# W-N-DM-V31_Display.net
KiCad netlist of a schematic drawn in Altium Designer
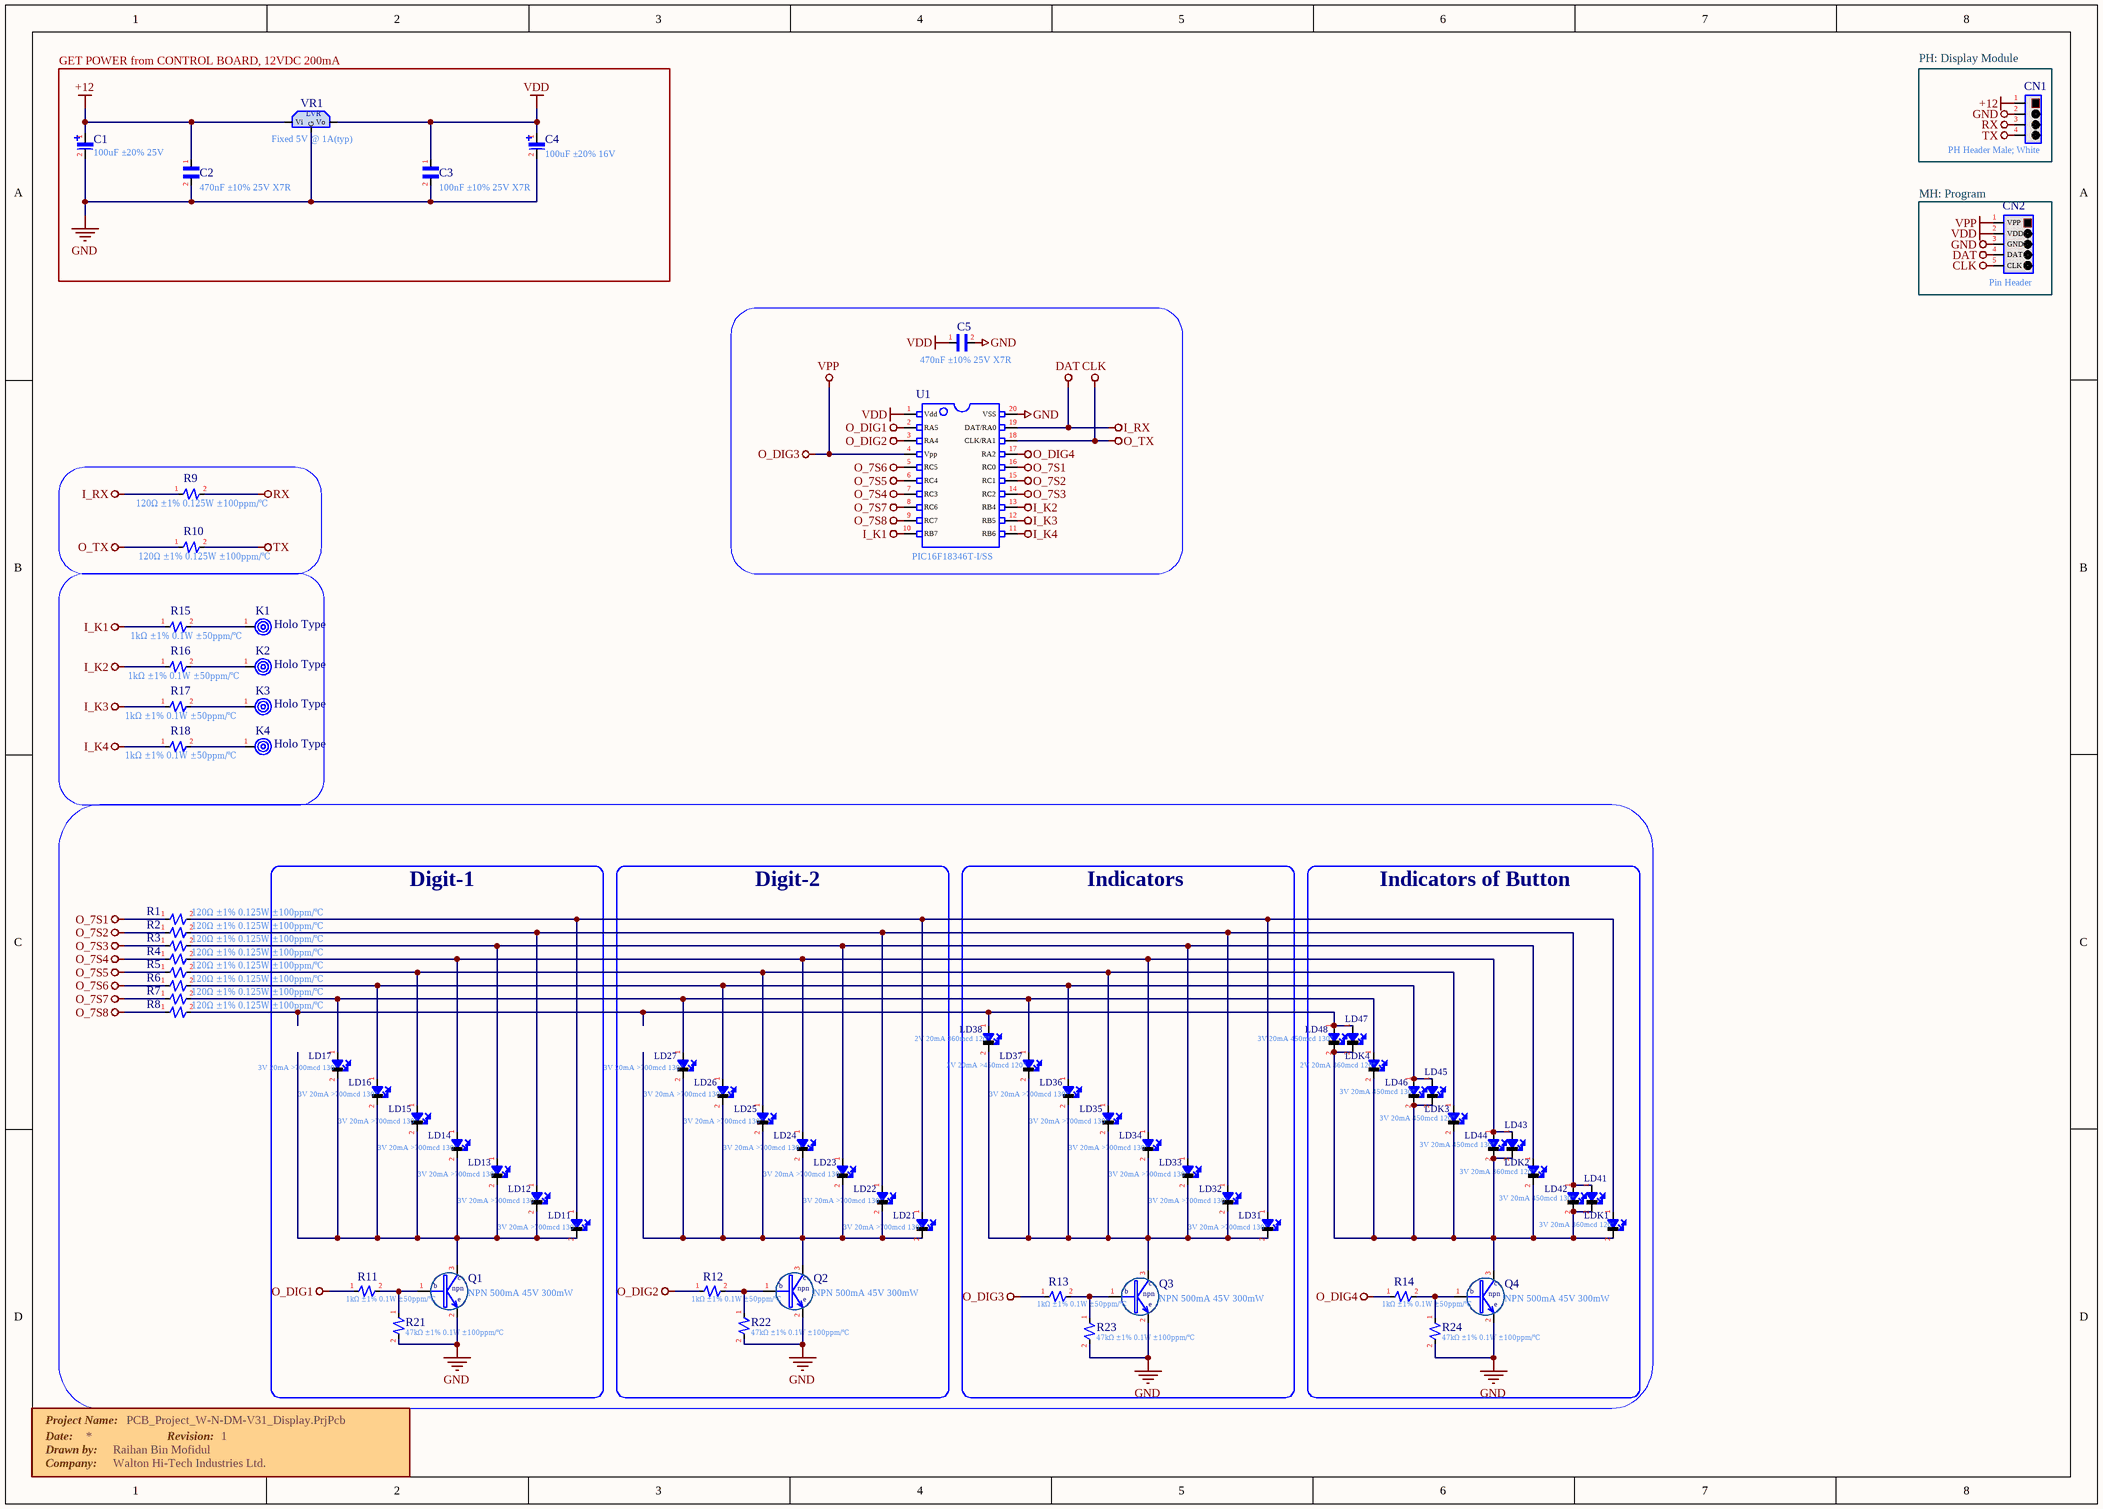
[diagram p0: W-N-DM-V31_Display.SchDoc]

(export (version "E")
  (design (tool "Eeschema 10.0.6"))
  (components
    (comp (ref "C1")
      (value "100uF ±20% 25V")
      (footprint "C_SMD_Ø6.3*5.4mm")
      (description "SMD,6.3x5.4mm Aluminum Electrolytic Capacitors - SMD RoHS")
      (libsource (lib "RBM_ALTIUM_SCH_LIBRARY") (part "Capacitor{gt}{gt} Polar"))
    )
    (comp (ref "C2")
      (value "470nF ±10% 25V X7R")
      (footprint "C_0603")
      (description "0603 Multilayer Ceramic Capacitors MLCC - SMD/SMT RoHS")
      (libsource (lib "RBM_ALTIUM_SCH_LIBRARY") (part "Capacitor{gt}{gt} Non-Polar"))
    )
    (comp (ref "C3")
      (value "100nF ±10% 25V X7R")
      (footprint "C_0603")
      (description "0603 Multilayer Ceramic Capacitors MLCC - SMD/SMT RoHS")
      (libsource (lib "RBM_ALTIUM_SCH_LIBRARY") (part "Capacitor{gt}{gt} Non-Polar"))
    )
    (comp (ref "C4")
      (value "100uF ±20% 16V")
      (footprint "C_SMD_Ø6.3*5.4mm")
      (description "SMD,6.3x5.4mm Aluminum Electrolytic Capacitors - SMD RoHS")
      (libsource (lib "RBM_ALTIUM_SCH_LIBRARY") (part "Capacitor{gt}{gt} Polar"))
    )
    (comp (ref "C5")
      (value "470nF ±10% 25V X7R")
      (footprint "C_0603")
      (description "0603 Multilayer Ceramic Capacitors MLCC - SMD/SMT RoHS")
      (libsource (lib "") (part "Capacitor{gt}{gt} Non-Polar_1"))
    )
    (comp (ref "CN1")
      (value "PH Header Male; White")
      (footprint "CN_4P_A2001WR-S-XP-LCP")
      (description "A2001WR-S-4P; Pin 0.079\"(2.00mm) 4 SMD,P=2mm Wire To Board / Wire To Wire Connector RoHS")
      (libsource (lib "RBM_ALTIUM_SCH_LIBRARY") (part "Connector{gt}{gt} 4Pins"))
    )
    (comp (ref "CN2")
      (value "Pin Header")
      (footprint "CN_PIC_MCU_Debugger_RightAngle")
      (libsource (lib "RBM_ALTIUM_SCH_LIBRARY") (part "Connector{gt}{gt} PIC Program"))
    )
    (comp (ref "K1")
      (value "Holo Type")
      (footprint "K_Cap-Touch_with_LED-Option")
      (libsource (lib "RBM_ALTIUM_SCH_LIBRARY") (part "Key{gt}{gt} Cap Touch"))
    )
    (comp (ref "K2")
      (value "Holo Type")
      (footprint "K_Cap-Touch_with_LED-Option")
      (libsource (lib "RBM_ALTIUM_SCH_LIBRARY") (part "Key{gt}{gt} Cap Touch"))
    )
    (comp (ref "K3")
      (value "Holo Type")
      (footprint "K_Cap-Touch_with_LED-Option")
      (libsource (lib "RBM_ALTIUM_SCH_LIBRARY") (part "Key{gt}{gt} Cap Touch"))
    )
    (comp (ref "K4")
      (value "Holo Type")
      (footprint "K_Cap-Touch_with_LED-Option")
      (libsource (lib "RBM_ALTIUM_SCH_LIBRARY") (part "Key{gt}{gt} Cap Touch"))
    )
    (comp (ref "LD11")
      (value "3V 20mA >700mcd 130°")
      (footprint "LED_SMD0603")
      (description "MHT192WDT-ICE; ICE-BLUE Color - 0603 Light Emitting Diodes (LED) RoHS")
      (libsource (lib "RBM_ALTIUM_SCH_LIBRARY") (part "LED{gt}{gt} General Purpose"))
    )
    (comp (ref "LD12")
      (value "3V 20mA >700mcd 130°")
      (footprint "LED_SMD0603")
      (description "MHT192WDT-ICE; ICE-BLUE Color - 0603 Light Emitting Diodes (LED) RoHS")
      (libsource (lib "RBM_ALTIUM_SCH_LIBRARY") (part "LED{gt}{gt} General Purpose"))
    )
    (comp (ref "LD13")
      (value "3V 20mA >700mcd 130°")
      (footprint "LED_SMD0603")
      (description "MHT192WDT-ICE; ICE-BLUE Color - 0603 Light Emitting Diodes (LED) RoHS")
      (libsource (lib "RBM_ALTIUM_SCH_LIBRARY") (part "LED{gt}{gt} General Purpose"))
    )
    (comp (ref "LD14")
      (value "3V 20mA >700mcd 130°")
      (footprint "LED_SMD0603")
      (description "MHT192WDT-ICE; ICE-BLUE Color - 0603 Light Emitting Diodes (LED) RoHS")
      (libsource (lib "RBM_ALTIUM_SCH_LIBRARY") (part "LED{gt}{gt} General Purpose"))
    )
    (comp (ref "LD15")
      (value "3V 20mA >700mcd 130°")
      (footprint "LED_SMD0603")
      (description "MHT192WDT-ICE; ICE-BLUE Color - 0603 Light Emitting Diodes (LED) RoHS")
      (libsource (lib "RBM_ALTIUM_SCH_LIBRARY") (part "LED{gt}{gt} General Purpose"))
    )
    (comp (ref "LD16")
      (value "3V 20mA >700mcd 130°")
      (footprint "LED_SMD0603")
      (description "MHT192WDT-ICE; ICE-BLUE Color - 0603 Light Emitting Diodes (LED) RoHS")
      (libsource (lib "RBM_ALTIUM_SCH_LIBRARY") (part "LED{gt}{gt} General Purpose"))
    )
    (comp (ref "LD17")
      (value "3V 20mA >700mcd 130°")
      (footprint "LED_SMD0603")
      (description "MHT192WDT-ICE; ICE-BLUE Color - 0603 Light Emitting Diodes (LED) RoHS")
      (libsource (lib "RBM_ALTIUM_SCH_LIBRARY") (part "LED{gt}{gt} General Purpose"))
    )
    (comp (ref "LD21")
      (value "3V 20mA >700mcd 130°")
      (footprint "LED_SMD0603")
      (description "MHT192WDT-ICE; ICE-BLUE Color - 0603 Light Emitting Diodes (LED) RoHS")
      (libsource (lib "RBM_ALTIUM_SCH_LIBRARY") (part "LED{gt}{gt} General Purpose"))
    )
    (comp (ref "LD22")
      (value "3V 20mA >700mcd 130°")
      (footprint "LED_SMD0603")
      (description "MHT192WDT-ICE; ICE-BLUE Color - 0603 Light Emitting Diodes (LED) RoHS")
      (libsource (lib "RBM_ALTIUM_SCH_LIBRARY") (part "LED{gt}{gt} General Purpose"))
    )
    (comp (ref "LD23")
      (value "3V 20mA >700mcd 130°")
      (footprint "LED_SMD0603")
      (description "MHT192WDT-ICE; ICE-BLUE Color - 0603 Light Emitting Diodes (LED) RoHS")
      (libsource (lib "RBM_ALTIUM_SCH_LIBRARY") (part "LED{gt}{gt} General Purpose"))
    )
    (comp (ref "LD24")
      (value "3V 20mA >700mcd 130°")
      (footprint "LED_SMD0603")
      (description "MHT192WDT-ICE; ICE-BLUE Color - 0603 Light Emitting Diodes (LED) RoHS")
      (libsource (lib "RBM_ALTIUM_SCH_LIBRARY") (part "LED{gt}{gt} General Purpose"))
    )
    (comp (ref "LD25")
      (value "3V 20mA >700mcd 130°")
      (footprint "LED_SMD0603")
      (description "MHT192WDT-ICE; ICE-BLUE Color - 0603 Light Emitting Diodes (LED) RoHS")
      (libsource (lib "RBM_ALTIUM_SCH_LIBRARY") (part "LED{gt}{gt} General Purpose"))
    )
    (comp (ref "LD26")
      (value "3V 20mA >700mcd 130°")
      (footprint "LED_SMD0603")
      (description "MHT192WDT-ICE; ICE-BLUE Color - 0603 Light Emitting Diodes (LED) RoHS")
      (libsource (lib "RBM_ALTIUM_SCH_LIBRARY") (part "LED{gt}{gt} General Purpose"))
    )
    (comp (ref "LD27")
      (value "3V 20mA >700mcd 130°")
      (footprint "LED_SMD0603")
      (description "MHT192WDT-ICE; ICE-BLUE Color - 0603 Light Emitting Diodes (LED) RoHS")
      (libsource (lib "RBM_ALTIUM_SCH_LIBRARY") (part "LED{gt}{gt} General Purpose"))
    )
    (comp (ref "LD31")
      (value "3V 20mA >700mcd 130°")
      (footprint "LED_SMD0603")
      (description "MHT192WDT-ICE; ICE-BLUE Color - 0603 Light Emitting Diodes (LED) RoHS")
      (libsource (lib "RBM_ALTIUM_SCH_LIBRARY") (part "LED{gt}{gt} General Purpose"))
    )
    (comp (ref "LD32")
      (value "3V 20mA >700mcd 130°")
      (footprint "LED_SMD0603")
      (description "MHT192WDT-ICE; ICE-BLUE Color - 0603 Light Emitting Diodes (LED) RoHS")
      (libsource (lib "RBM_ALTIUM_SCH_LIBRARY") (part "LED{gt}{gt} General Purpose"))
    )
    (comp (ref "LD33")
      (value "3V 20mA >700mcd 130°")
      (footprint "LED_SMD0603")
      (description "MHT192WDT-ICE; ICE-BLUE Color - 0603 Light Emitting Diodes (LED) RoHS")
      (libsource (lib "RBM_ALTIUM_SCH_LIBRARY") (part "LED{gt}{gt} General Purpose"))
    )
    (comp (ref "LD34")
      (value "3V 20mA >700mcd 130°")
      (footprint "LED_SMD0603")
      (description "MHT192WDT-ICE; ICE-BLUE Color - 0603 Light Emitting Diodes (LED) RoHS")
      (libsource (lib "RBM_ALTIUM_SCH_LIBRARY") (part "LED{gt}{gt} General Purpose"))
    )
    (comp (ref "LD35")
      (value "3V 20mA >700mcd 130°")
      (footprint "LED_SMD0603")
      (description "MHT192WDT-ICE; ICE-BLUE Color - 0603 Light Emitting Diodes (LED) RoHS")
      (libsource (lib "RBM_ALTIUM_SCH_LIBRARY") (part "LED{gt}{gt} General Purpose"))
    )
    (comp (ref "LD36")
      (value "3V 20mA >700mcd 130°")
      (footprint "LED_SMD0603")
      (description "MHT192WDT-ICE; ICE-BLUE Color - 0603 Light Emitting Diodes (LED) RoHS")
      (libsource (lib "RBM_ALTIUM_SCH_LIBRARY") (part "LED{gt}{gt} General Purpose"))
    )
    (comp (ref "LD37")
      (value "2V 20mA >450mcd 120°")
      (footprint "LED_SMD0603")
      (description "MHT192URCT; Brilliant Red Color - 0603 Light Emitting Diodes (LED) RoHS")
      (libsource (lib "RBM_ALTIUM_SCH_LIBRARY") (part "LED{gt}{gt} General Purpose"))
    )
    (comp (ref "LD38")
      (value "2V 20mA 360mcd 120°")
      (footprint "LED_SMD0603")
      (description "MHT192USCT; Brilliant Orange Color - 0603 Light Emitting Diodes (LED) RoHS")
      (libsource (lib "RBM_ALTIUM_SCH_LIBRARY") (part "LED{gt}{gt} General Purpose"))
    )
    (comp (ref "LD41")
      (value "3V 20mA 450mcd 130°")
      (footprint "LED_SMD0603")
      (description "MHT192WDT-C2; WHITE Color - 0603 Light Emitting Diodes (LED) RoHS")
      (libsource (lib "RBM_ALTIUM_SCH_LIBRARY") (part "LED{gt}{gt} General Purpose"))
    )
    (comp (ref "LD42")
      (value "3V 20mA 450mcd 130°")
      (footprint "LED_SMD0603")
      (description "MHT192WDT-C2; WHITE Color - 0603 Light Emitting Diodes (LED) RoHS")
      (libsource (lib "RBM_ALTIUM_SCH_LIBRARY") (part "LED{gt}{gt} General Purpose"))
    )
    (comp (ref "LD43")
      (value "3V 20mA 450mcd 130°")
      (footprint "LED_SMD0603")
      (description "MHT192WDT-C2; WHITE Color - 0603 Light Emitting Diodes (LED) RoHS")
      (libsource (lib "RBM_ALTIUM_SCH_LIBRARY") (part "LED{gt}{gt} General Purpose"))
    )
    (comp (ref "LD44")
      (value "3V 20mA 450mcd 130°")
      (footprint "LED_SMD0603")
      (description "MHT192WDT-C2; WHITE Color - 0603 Light Emitting Diodes (LED) RoHS")
      (libsource (lib "RBM_ALTIUM_SCH_LIBRARY") (part "LED{gt}{gt} General Purpose"))
    )
    (comp (ref "LD45")
      (value "3V 20mA 450mcd 130°")
      (footprint "LED_SMD0603")
      (description "MHT192WDT-C2; WHITE Color - 0603 Light Emitting Diodes (LED) RoHS")
      (libsource (lib "RBM_ALTIUM_SCH_LIBRARY") (part "LED{gt}{gt} General Purpose"))
    )
    (comp (ref "LD46")
      (value "3V 20mA 450mcd 130°")
      (footprint "LED_SMD0603")
      (description "MHT192WDT-C2; WHITE Color - 0603 Light Emitting Diodes (LED) RoHS")
      (libsource (lib "RBM_ALTIUM_SCH_LIBRARY") (part "LED{gt}{gt} General Purpose"))
    )
    (comp (ref "LD47")
      (value "3V 20mA 450mcd 130°")
      (footprint "LED_SMD0603")
      (description "MHT192WDT-C2; WHITE Color - 0603 Light Emitting Diodes (LED) RoHS")
      (libsource (lib "RBM_ALTIUM_SCH_LIBRARY") (part "LED{gt}{gt} General Purpose"))
    )
    (comp (ref "LD48")
      (value "3V 20mA 450mcd 130°")
      (footprint "LED_SMD0603")
      (description "MHT192WDT-C2; WHITE Color - 0603 Light Emitting Diodes (LED) RoHS")
      (libsource (lib "") (part "LED{gt}{gt} General Purpose_1"))
    )
    (comp (ref "LDK1")
      (value "3V 20mA 360mcd 120°")
      (footprint "LED_SMD0603")
      (description "MHT192UBCT; Brilliant Blue Color - 0603 Light Emitting Diodes (LED) RoHS")
      (libsource (lib "RBM_ALTIUM_SCH_LIBRARY") (part "LED{gt}{gt} General Purpose"))
    )
    (comp (ref "LDK2")
      (value "3V 20mA 360mcd 120°")
      (footprint "LED_SMD0603")
      (description "MHT192UBCT; Brilliant Blue Color - 0603 Light Emitting Diodes (LED) RoHS")
      (libsource (lib "RBM_ALTIUM_SCH_LIBRARY") (part "LED{gt}{gt} General Purpose"))
    )
    (comp (ref "LDK3")
      (value "3V 20mA 450mcd 120°")
      (footprint "LED_SMD0603")
      (description "MHT192UGCT; Brilliant Green Color - 0603 Light Emitting Diodes (LED) RoHS")
      (libsource (lib "RBM_ALTIUM_SCH_LIBRARY") (part "LED{gt}{gt} General Purpose"))
    )
    (comp (ref "LDK4")
      (value "2V 20mA 360mcd 120°")
      (footprint "LED_SMD0603")
      (description "MHT192USCT; Brilliant Orange Color - 0603 Light Emitting Diodes (LED) RoHS")
      (libsource (lib "RBM_ALTIUM_SCH_LIBRARY") (part "LED{gt}{gt} General Purpose"))
    )
    (comp (ref "Q1")
      (value "NPN 500mA 45V 300mW")
      (footprint "Q_SOT-23_NPN")
      (description "BC817-40; SOT-23(SOT-23-3) Transistors (NPN/PNP) RoHS")
      (libsource (lib "RBM_ALTIUM_SCH_LIBRARY") (part "Transistor{gt}{gt} BJT npn"))
    )
    (comp (ref "Q2")
      (value "NPN 500mA 45V 300mW")
      (footprint "Q_SOT-23_NPN")
      (description "BC817-40; SOT-23(SOT-23-3) Transistors (NPN/PNP) RoHS")
      (libsource (lib "RBM_ALTIUM_SCH_LIBRARY") (part "Transistor{gt}{gt} BJT npn"))
    )
    (comp (ref "Q3")
      (value "NPN 500mA 45V 300mW")
      (footprint "Q_SOT-23_NPN")
      (description "BC817-40; SOT-23(SOT-23-3) Transistors (NPN/PNP) RoHS")
      (libsource (lib "RBM_ALTIUM_SCH_LIBRARY") (part "Transistor{gt}{gt} BJT npn"))
    )
    (comp (ref "Q4")
      (value "NPN 500mA 45V 300mW")
      (footprint "Q_SOT-23_NPN")
      (description "BC817-40; SOT-23(SOT-23-3) Transistors (NPN/PNP) RoHS")
      (libsource (lib "RBM_ALTIUM_SCH_LIBRARY") (part "Transistor{gt}{gt} BJT npn"))
    )
    (comp (ref "R1")
      (value "120Ω ±1% 0.125W ±100ppm/℃")
      (footprint "R_0603")
      (description "RK73H1JTTD1200F; 0603 Chip Resistor - Surface Mount RoHS")
      (libsource (lib "RBM_ALTIUM_SCH_LIBRARY") (part "Resistor{gt}{gt} General Purpose"))
    )
    (comp (ref "R2")
      (value "120Ω ±1% 0.125W ±100ppm/℃")
      (footprint "R_0603")
      (description "RK73H1JTTD1200F; 0603 Chip Resistor - Surface Mount RoHS")
      (libsource (lib "RBM_ALTIUM_SCH_LIBRARY") (part "Resistor{gt}{gt} General Purpose"))
    )
    (comp (ref "R3")
      (value "120Ω ±1% 0.125W ±100ppm/℃")
      (footprint "R_0603")
      (description "RK73H1JTTD1200F; 0603 Chip Resistor - Surface Mount RoHS")
      (libsource (lib "RBM_ALTIUM_SCH_LIBRARY") (part "Resistor{gt}{gt} General Purpose"))
    )
    (comp (ref "R4")
      (value "120Ω ±1% 0.125W ±100ppm/℃")
      (footprint "R_0603")
      (description "RK73H1JTTD1200F; 0603 Chip Resistor - Surface Mount RoHS")
      (libsource (lib "RBM_ALTIUM_SCH_LIBRARY") (part "Resistor{gt}{gt} General Purpose"))
    )
    (comp (ref "R5")
      (value "120Ω ±1% 0.125W ±100ppm/℃")
      (footprint "R_0603")
      (description "RK73H1JTTD1200F; 0603 Chip Resistor - Surface Mount RoHS")
      (libsource (lib "RBM_ALTIUM_SCH_LIBRARY") (part "Resistor{gt}{gt} General Purpose"))
    )
    (comp (ref "R6")
      (value "120Ω ±1% 0.125W ±100ppm/℃")
      (footprint "R_0603")
      (description "RK73H1JTTD1200F; 0603 Chip Resistor - Surface Mount RoHS")
      (libsource (lib "RBM_ALTIUM_SCH_LIBRARY") (part "Resistor{gt}{gt} General Purpose"))
    )
    (comp (ref "R7")
      (value "120Ω ±1% 0.125W ±100ppm/℃")
      (footprint "R_0603")
      (description "RK73H1JTTD1200F; 0603 Chip Resistor - Surface Mount RoHS")
      (libsource (lib "RBM_ALTIUM_SCH_LIBRARY") (part "Resistor{gt}{gt} General Purpose"))
    )
    (comp (ref "R8")
      (value "120Ω ±1% 0.125W ±100ppm/℃")
      (footprint "R_0603")
      (description "RK73H1JTTD1200F; 0603 Chip Resistor - Surface Mount RoHS")
      (libsource (lib "RBM_ALTIUM_SCH_LIBRARY") (part "Resistor{gt}{gt} General Purpose"))
    )
    (comp (ref "R9")
      (value "120Ω ±1% 0.125W ±100ppm/℃")
      (footprint "R_0603")
      (description "RK73H1JTTD1200F; 0603 Chip Resistor - Surface Mount RoHS")
      (libsource (lib "RBM_ALTIUM_SCH_LIBRARY") (part "Resistor{gt}{gt} General Purpose"))
    )
    (comp (ref "R10")
      (value "120Ω ±1% 0.125W ±100ppm/℃")
      (footprint "R_0603")
      (description "RK73H1JTTD1200F; 0603 Chip Resistor - Surface Mount RoHS")
      (libsource (lib "RBM_ALTIUM_SCH_LIBRARY") (part "Resistor{gt}{gt} General Purpose"))
    )
    (comp (ref "R11")
      (value "1kΩ ±1% 0.1W ±50ppm/℃")
      (footprint "R_0603")
      (description "RK73G1JTTD1001F; 0603 Chip Resistor - Surface Mount RoHS")
      (libsource (lib "RBM_ALTIUM_SCH_LIBRARY") (part "Resistor{gt}{gt} General Purpose"))
    )
    (comp (ref "R12")
      (value "1kΩ ±1% 0.1W ±50ppm/℃")
      (footprint "R_0603")
      (description "RK73G1JTTD1001F; 0603 Chip Resistor - Surface Mount RoHS")
      (libsource (lib "RBM_ALTIUM_SCH_LIBRARY") (part "Resistor{gt}{gt} General Purpose"))
    )
    (comp (ref "R13")
      (value "1kΩ ±1% 0.1W ±50ppm/℃")
      (footprint "R_0603")
      (description "RK73G1JTTD1001F; 0603 Chip Resistor - Surface Mount RoHS")
      (libsource (lib "RBM_ALTIUM_SCH_LIBRARY") (part "Resistor{gt}{gt} General Purpose"))
    )
    (comp (ref "R14")
      (value "1kΩ ±1% 0.1W ±50ppm/℃")
      (footprint "R_0603")
      (description "RK73G1JTTD1001F; 0603 Chip Resistor - Surface Mount RoHS")
      (libsource (lib "RBM_ALTIUM_SCH_LIBRARY") (part "Resistor{gt}{gt} General Purpose"))
    )
    (comp (ref "R15")
      (value "1kΩ ±1% 0.1W ±50ppm/℃")
      (footprint "R_0603")
      (description "RK73G1JTTD1001F; 0603 Chip Resistor - Surface Mount RoHS")
      (libsource (lib "RBM_ALTIUM_SCH_LIBRARY") (part "Resistor{gt}{gt} General Purpose"))
    )
    (comp (ref "R16")
      (value "1kΩ ±1% 0.1W ±50ppm/℃")
      (footprint "R_0603")
      (description "RK73G1JTTD1001F; 0603 Chip Resistor - Surface Mount RoHS")
      (libsource (lib "RBM_ALTIUM_SCH_LIBRARY") (part "Resistor{gt}{gt} General Purpose"))
    )
    (comp (ref "R17")
      (value "1kΩ ±1% 0.1W ±50ppm/℃")
      (footprint "R_0603")
      (description "RK73G1JTTD1001F; 0603 Chip Resistor - Surface Mount RoHS")
      (libsource (lib "RBM_ALTIUM_SCH_LIBRARY") (part "Resistor{gt}{gt} General Purpose"))
    )
    (comp (ref "R18")
      (value "1kΩ ±1% 0.1W ±50ppm/℃")
      (footprint "R_0603")
      (description "RK73G1JTTD1001F; 0603 Chip Resistor - Surface Mount RoHS")
      (libsource (lib "RBM_ALTIUM_SCH_LIBRARY") (part "Resistor{gt}{gt} General Purpose"))
    )
    (comp (ref "R21")
      (value "47kΩ ±1% 0.1W ±100ppm/℃")
      (footprint "R_0603")
      (description "RK73H1JTTD4702F; 0603 Chip Resistor - Surface Mount RoHS")
      (libsource (lib "RBM_ALTIUM_SCH_LIBRARY") (part "Resistor{gt}{gt} General Purpose"))
    )
    (comp (ref "R22")
      (value "47kΩ ±1% 0.1W ±100ppm/℃")
      (footprint "R_0603")
      (description "RK73H1JTTD4702F; 0603 Chip Resistor - Surface Mount RoHS")
      (libsource (lib "RBM_ALTIUM_SCH_LIBRARY") (part "Resistor{gt}{gt} General Purpose"))
    )
    (comp (ref "R23")
      (value "47kΩ ±1% 0.1W ±100ppm/℃")
      (footprint "R_0603")
      (description "RK73H1JTTD4702F; 0603 Chip Resistor - Surface Mount RoHS")
      (libsource (lib "RBM_ALTIUM_SCH_LIBRARY") (part "Resistor{gt}{gt} General Purpose"))
    )
    (comp (ref "R24")
      (value "47kΩ ±1% 0.1W ±100ppm/℃")
      (footprint "R_0603")
      (description "RK73H1JTTD4702F; 0603 Chip Resistor - Surface Mount RoHS")
      (libsource (lib "RBM_ALTIUM_SCH_LIBRARY") (part "Resistor{gt}{gt} General Purpose"))
    )
    (comp (ref "U1")
      (value "PIC16F18346T-I/SS")
      (footprint "U_PIC_20pin_SSOP")
      (libsource (lib "RBM_ALTIUM_SCH_LIBRARY") (part "IC{gt}{gt} PIC 20Pins"))
    )
    (comp (ref "VR1")
      (value "Fixed 5V @ 1A(typ)")
      (footprint "VR_TO-252-2(DPAK)")
      (description "CJ78D05/MC7805BDTRKG; TO-252-2(DPAK) Dropout Regulators(LDO) RoHS")
      (libsource (lib "RBM_ALTIUM_SCH_LIBRARY") (part "Voltage Regulator"))
    )
  )
  (nets
    (net (code "1") (name "+12") (class "Default")
      (node (ref "C1") (pin "1") (pinfunction "1_1") (pintype "passive"))
      (node (ref "C2") (pin "1") (pinfunction "1_1") (pintype "passive"))
      (node (ref "CN1") (pin "1") (pinfunction "1_1") (pintype "passive"))
      (node (ref "VR1") (pin "V-IN") (pinfunction "Vi_V-IN") (pintype "passive"))
    )
    (net (code "2") (name "CLK") (class "Default")
      (node (ref "CN2") (pin "5") (pinfunction "CLK_5") (pintype "passive"))
      (node (ref "R10") (pin "1") (pinfunction "1_1") (pintype "passive"))
      (node (ref "U1") (pin "18") (pinfunction "CLK/RA1_18") (pintype "passive"))
    )
    (net (code "3") (name "DAT") (class "Default")
      (node (ref "CN2") (pin "4") (pinfunction "DAT_4") (pintype "passive"))
      (node (ref "R9") (pin "1") (pinfunction "1_1") (pintype "passive"))
      (node (ref "U1") (pin "19") (pinfunction "DAT/RA0_19") (pintype "passive"))
    )
    (net (code "4") (name "GND") (class "Default")
      (node (ref "C1") (pin "2") (pinfunction "2_2") (pintype "passive"))
      (node (ref "C2") (pin "2") (pinfunction "2_2") (pintype "passive"))
      (node (ref "C3") (pin "2") (pinfunction "2_2") (pintype "passive"))
      (node (ref "C4") (pin "2") (pinfunction "2_2") (pintype "passive"))
      (node (ref "C5") (pin "2") (pinfunction "2_2") (pintype "passive"))
      (node (ref "CN1") (pin "2") (pinfunction "2_2") (pintype "passive"))
      (node (ref "CN2") (pin "3") (pinfunction "GND_3") (pintype "passive"))
      (node (ref "Q1") (pin "2") (pinfunction "Emitter_2") (pintype "passive"))
      (node (ref "Q2") (pin "2") (pinfunction "Emitter_2") (pintype "passive"))
      (node (ref "Q3") (pin "2") (pinfunction "Emitter_2") (pintype "passive"))
      (node (ref "Q4") (pin "2") (pinfunction "Emitter_2") (pintype "passive"))
      (node (ref "R21") (pin "2") (pinfunction "2_2") (pintype "passive"))
      (node (ref "R22") (pin "2") (pinfunction "2_2") (pintype "passive"))
      (node (ref "R23") (pin "2") (pinfunction "2_2") (pintype "passive"))
      (node (ref "R24") (pin "2") (pinfunction "2_2") (pintype "passive"))
      (node (ref "U1") (pin "20") (pinfunction "VSS_20") (pintype "passive"))
      (node (ref "VR1") (pin "GND") (pinfunction "G_GND") (pintype "passive"))
    )
    (net (code "5") (name "I_K1") (class "Default")
      (node (ref "R15") (pin "1") (pinfunction "1_1") (pintype "passive"))
      (node (ref "U1") (pin "10") (pinfunction "RB7_10") (pintype "passive"))
    )
    (net (code "6") (name "I_K2") (class "Default")
      (node (ref "R16") (pin "1") (pinfunction "1_1") (pintype "passive"))
      (node (ref "U1") (pin "13") (pinfunction "RB4_13") (pintype "passive"))
    )
    (net (code "7") (name "I_K3") (class "Default")
      (node (ref "R17") (pin "1") (pinfunction "1_1") (pintype "passive"))
      (node (ref "U1") (pin "12") (pinfunction "RB5_12") (pintype "passive"))
    )
    (net (code "8") (name "I_K4") (class "Default")
      (node (ref "R18") (pin "1") (pinfunction "1_1") (pintype "passive"))
      (node (ref "U1") (pin "11") (pinfunction "RB6_11") (pintype "passive"))
    )
    (net (code "9") (name "Net-(K1-Pad1)") (class "Default")
      (node (ref "K1") (pin "1") (pinfunction "1_1") (pintype "passive"))
      (node (ref "R15") (pin "2") (pinfunction "2_2") (pintype "passive"))
    )
    (net (code "10") (name "Net-(K2-Pad1)") (class "Default")
      (node (ref "K2") (pin "1") (pinfunction "1_1") (pintype "passive"))
      (node (ref "R16") (pin "2") (pinfunction "2_2") (pintype "passive"))
    )
    (net (code "11") (name "Net-(K3-Pad1)") (class "Default")
      (node (ref "K3") (pin "1") (pinfunction "1_1") (pintype "passive"))
      (node (ref "R17") (pin "2") (pinfunction "2_2") (pintype "passive"))
    )
    (net (code "12") (name "Net-(K4-Pad1)") (class "Default")
      (node (ref "K4") (pin "1") (pinfunction "1_1") (pintype "passive"))
      (node (ref "R18") (pin "2") (pinfunction "2_2") (pintype "passive"))
    )
    (net (code "13") (name "Net-(LD11-vdd)") (class "Default")
      (node (ref "LD11") (pin "1") (pinfunction "vdd_1") (pintype "passive"))
      (node (ref "LD21") (pin "1") (pinfunction "vdd_1") (pintype "passive"))
      (node (ref "LD31") (pin "1") (pinfunction "vdd_1") (pintype "passive"))
      (node (ref "LDK1") (pin "1") (pinfunction "vdd_1") (pintype "passive"))
      (node (ref "R1") (pin "2") (pinfunction "2_2") (pintype "passive"))
    )
    (net (code "14") (name "Net-(LD11-vss)") (class "Default")
      (node (ref "LD11") (pin "2") (pinfunction "vss_2") (pintype "passive"))
      (node (ref "LD12") (pin "2") (pinfunction "vss_2") (pintype "passive"))
      (node (ref "LD13") (pin "2") (pinfunction "vss_2") (pintype "passive"))
      (node (ref "LD14") (pin "2") (pinfunction "vss_2") (pintype "passive"))
      (node (ref "LD15") (pin "2") (pinfunction "vss_2") (pintype "passive"))
      (node (ref "LD16") (pin "2") (pinfunction "vss_2") (pintype "passive"))
      (node (ref "LD17") (pin "2") (pinfunction "vss_2") (pintype "passive"))
      (node (ref "Q1") (pin "3") (pinfunction "Collector_3") (pintype "passive"))
    )
    (net (code "15") (name "Net-(LD12-vdd)") (class "Default")
      (node (ref "LD12") (pin "1") (pinfunction "vdd_1") (pintype "passive"))
      (node (ref "LD22") (pin "1") (pinfunction "vdd_1") (pintype "passive"))
      (node (ref "LD32") (pin "1") (pinfunction "vdd_1") (pintype "passive"))
      (node (ref "LD41") (pin "1") (pinfunction "vdd_1") (pintype "passive"))
      (node (ref "LD42") (pin "1") (pinfunction "vdd_1") (pintype "passive"))
      (node (ref "R2") (pin "2") (pinfunction "2_2") (pintype "passive"))
    )
    (net (code "16") (name "Net-(LD13-vdd)") (class "Default")
      (node (ref "LD13") (pin "1") (pinfunction "vdd_1") (pintype "passive"))
      (node (ref "LD23") (pin "1") (pinfunction "vdd_1") (pintype "passive"))
      (node (ref "LD33") (pin "1") (pinfunction "vdd_1") (pintype "passive"))
      (node (ref "LDK2") (pin "1") (pinfunction "vdd_1") (pintype "passive"))
      (node (ref "R3") (pin "2") (pinfunction "2_2") (pintype "passive"))
    )
    (net (code "17") (name "Net-(LD14-vdd)") (class "Default")
      (node (ref "LD14") (pin "1") (pinfunction "vdd_1") (pintype "passive"))
      (node (ref "LD24") (pin "1") (pinfunction "vdd_1") (pintype "passive"))
      (node (ref "LD34") (pin "1") (pinfunction "vdd_1") (pintype "passive"))
      (node (ref "LD43") (pin "1") (pinfunction "vdd_1") (pintype "passive"))
      (node (ref "LD44") (pin "1") (pinfunction "vdd_1") (pintype "passive"))
      (node (ref "R4") (pin "2") (pinfunction "2_2") (pintype "passive"))
    )
    (net (code "18") (name "Net-(LD15-vdd)") (class "Default")
      (node (ref "LD15") (pin "1") (pinfunction "vdd_1") (pintype "passive"))
      (node (ref "LD25") (pin "1") (pinfunction "vdd_1") (pintype "passive"))
      (node (ref "LD35") (pin "1") (pinfunction "vdd_1") (pintype "passive"))
      (node (ref "LDK3") (pin "1") (pinfunction "vdd_1") (pintype "passive"))
      (node (ref "R5") (pin "2") (pinfunction "2_2") (pintype "passive"))
    )
    (net (code "19") (name "Net-(LD16-vdd)") (class "Default")
      (node (ref "LD16") (pin "1") (pinfunction "vdd_1") (pintype "passive"))
      (node (ref "LD26") (pin "1") (pinfunction "vdd_1") (pintype "passive"))
      (node (ref "LD36") (pin "1") (pinfunction "vdd_1") (pintype "passive"))
      (node (ref "LD45") (pin "1") (pinfunction "vdd_1") (pintype "passive"))
      (node (ref "LD46") (pin "1") (pinfunction "vdd_1") (pintype "passive"))
      (node (ref "R6") (pin "2") (pinfunction "2_2") (pintype "passive"))
    )
    (net (code "20") (name "Net-(LD17-vdd)") (class "Default")
      (node (ref "LD17") (pin "1") (pinfunction "vdd_1") (pintype "passive"))
      (node (ref "LD27") (pin "1") (pinfunction "vdd_1") (pintype "passive"))
      (node (ref "LD37") (pin "1") (pinfunction "vdd_1") (pintype "passive"))
      (node (ref "LDK4") (pin "1") (pinfunction "vdd_1") (pintype "passive"))
      (node (ref "R7") (pin "2") (pinfunction "2_2") (pintype "passive"))
    )
    (net (code "21") (name "Net-(LD21-vss)") (class "Default")
      (node (ref "LD21") (pin "2") (pinfunction "vss_2") (pintype "passive"))
      (node (ref "LD22") (pin "2") (pinfunction "vss_2") (pintype "passive"))
      (node (ref "LD23") (pin "2") (pinfunction "vss_2") (pintype "passive"))
      (node (ref "LD24") (pin "2") (pinfunction "vss_2") (pintype "passive"))
      (node (ref "LD25") (pin "2") (pinfunction "vss_2") (pintype "passive"))
      (node (ref "LD26") (pin "2") (pinfunction "vss_2") (pintype "passive"))
      (node (ref "LD27") (pin "2") (pinfunction "vss_2") (pintype "passive"))
      (node (ref "Q2") (pin "3") (pinfunction "Collector_3") (pintype "passive"))
    )
    (net (code "22") (name "Net-(LD31-vss)") (class "Default")
      (node (ref "LD31") (pin "2") (pinfunction "vss_2") (pintype "passive"))
      (node (ref "LD32") (pin "2") (pinfunction "vss_2") (pintype "passive"))
      (node (ref "LD33") (pin "2") (pinfunction "vss_2") (pintype "passive"))
      (node (ref "LD34") (pin "2") (pinfunction "vss_2") (pintype "passive"))
      (node (ref "LD35") (pin "2") (pinfunction "vss_2") (pintype "passive"))
      (node (ref "LD36") (pin "2") (pinfunction "vss_2") (pintype "passive"))
      (node (ref "LD37") (pin "2") (pinfunction "vss_2") (pintype "passive"))
      (node (ref "LD38") (pin "2") (pinfunction "vss_2") (pintype "passive"))
      (node (ref "Q3") (pin "3") (pinfunction "Collector_3") (pintype "passive"))
    )
    (net (code "23") (name "Net-(LD38-vdd)") (class "Default")
      (node (ref "LD38") (pin "1") (pinfunction "vdd_1") (pintype "passive"))
      (node (ref "LD47") (pin "1") (pinfunction "vdd_1") (pintype "passive"))
      (node (ref "LD48") (pin "1") (pinfunction "vdd_1") (pintype "passive"))
      (node (ref "R8") (pin "2") (pinfunction "2_2") (pintype "passive"))
    )
    (net (code "24") (name "Net-(LD41-vss)") (class "Default")
      (node (ref "LD41") (pin "2") (pinfunction "vss_2") (pintype "passive"))
      (node (ref "LD42") (pin "2") (pinfunction "vss_2") (pintype "passive"))
      (node (ref "LD43") (pin "2") (pinfunction "vss_2") (pintype "passive"))
      (node (ref "LD44") (pin "2") (pinfunction "vss_2") (pintype "passive"))
      (node (ref "LD45") (pin "2") (pinfunction "vss_2") (pintype "passive"))
      (node (ref "LD46") (pin "2") (pinfunction "vss_2") (pintype "passive"))
      (node (ref "LD47") (pin "2") (pinfunction "vss_2") (pintype "passive"))
      (node (ref "LD48") (pin "2") (pinfunction "vss_2") (pintype "passive"))
      (node (ref "LDK1") (pin "2") (pinfunction "vss_2") (pintype "passive"))
      (node (ref "LDK2") (pin "2") (pinfunction "vss_2") (pintype "passive"))
      (node (ref "LDK3") (pin "2") (pinfunction "vss_2") (pintype "passive"))
      (node (ref "LDK4") (pin "2") (pinfunction "vss_2") (pintype "passive"))
      (node (ref "Q4") (pin "3") (pinfunction "Collector_3") (pintype "passive"))
    )
    (net (code "25") (name "Net-(Q1-Base)") (class "Default")
      (node (ref "Q1") (pin "1") (pinfunction "Base_1") (pintype "passive"))
      (node (ref "R11") (pin "2") (pinfunction "2_2") (pintype "passive"))
      (node (ref "R21") (pin "1") (pinfunction "1_1") (pintype "passive"))
    )
    (net (code "26") (name "Net-(Q2-Base)") (class "Default")
      (node (ref "Q2") (pin "1") (pinfunction "Base_1") (pintype "passive"))
      (node (ref "R12") (pin "2") (pinfunction "2_2") (pintype "passive"))
      (node (ref "R22") (pin "1") (pinfunction "1_1") (pintype "passive"))
    )
    (net (code "27") (name "Net-(Q3-Base)") (class "Default")
      (node (ref "Q3") (pin "1") (pinfunction "Base_1") (pintype "passive"))
      (node (ref "R13") (pin "2") (pinfunction "2_2") (pintype "passive"))
      (node (ref "R23") (pin "1") (pinfunction "1_1") (pintype "passive"))
    )
    (net (code "28") (name "Net-(Q4-Base)") (class "Default")
      (node (ref "Q4") (pin "1") (pinfunction "Base_1") (pintype "passive"))
      (node (ref "R14") (pin "2") (pinfunction "2_2") (pintype "passive"))
      (node (ref "R24") (pin "1") (pinfunction "1_1") (pintype "passive"))
    )
    (net (code "29") (name "O_7S1") (class "Default")
      (node (ref "R1") (pin "1") (pinfunction "1_1") (pintype "passive"))
      (node (ref "U1") (pin "16") (pinfunction "RC0_16") (pintype "passive"))
    )
    (net (code "30") (name "O_7S2") (class "Default")
      (node (ref "R2") (pin "1") (pinfunction "1_1") (pintype "passive"))
      (node (ref "U1") (pin "15") (pinfunction "RC1_15") (pintype "passive"))
    )
    (net (code "31") (name "O_7S3") (class "Default")
      (node (ref "R3") (pin "1") (pinfunction "1_1") (pintype "passive"))
      (node (ref "U1") (pin "14") (pinfunction "RC2_14") (pintype "passive"))
    )
    (net (code "32") (name "O_7S4") (class "Default")
      (node (ref "R4") (pin "1") (pinfunction "1_1") (pintype "passive"))
      (node (ref "U1") (pin "7") (pinfunction "RC3_7") (pintype "passive"))
    )
    (net (code "33") (name "O_7S5") (class "Default")
      (node (ref "R5") (pin "1") (pinfunction "1_1") (pintype "passive"))
      (node (ref "U1") (pin "6") (pinfunction "RC4_6") (pintype "passive"))
    )
    (net (code "34") (name "O_7S6") (class "Default")
      (node (ref "R6") (pin "1") (pinfunction "1_1") (pintype "passive"))
      (node (ref "U1") (pin "5") (pinfunction "RC5_5") (pintype "passive"))
    )
    (net (code "35") (name "O_7S7") (class "Default")
      (node (ref "R7") (pin "1") (pinfunction "1_1") (pintype "passive"))
      (node (ref "U1") (pin "8") (pinfunction "RC6_8") (pintype "passive"))
    )
    (net (code "36") (name "O_7S8") (class "Default")
      (node (ref "R8") (pin "1") (pinfunction "1_1") (pintype "passive"))
      (node (ref "U1") (pin "9") (pinfunction "RC7_9") (pintype "passive"))
    )
    (net (code "37") (name "O_DIG1") (class "Default")
      (node (ref "R11") (pin "1") (pinfunction "1_1") (pintype "passive"))
      (node (ref "U1") (pin "2") (pinfunction "RA5_2") (pintype "passive"))
    )
    (net (code "38") (name "O_DIG2") (class "Default")
      (node (ref "R12") (pin "1") (pinfunction "1_1") (pintype "passive"))
      (node (ref "U1") (pin "3") (pinfunction "RA4_3") (pintype "passive"))
    )
    (net (code "39") (name "O_DIG3") (class "Default")
      (node (ref "CN2") (pin "1") (pinfunction "VPP_1") (pintype "passive"))
      (node (ref "R13") (pin "1") (pinfunction "1_1") (pintype "passive"))
      (node (ref "U1") (pin "4") (pinfunction "Vpp_4") (pintype "passive"))
    )
    (net (code "40") (name "O_DIG4") (class "Default")
      (node (ref "R14") (pin "1") (pinfunction "1_1") (pintype "passive"))
      (node (ref "U1") (pin "17") (pinfunction "RA2_17") (pintype "passive"))
    )
    (net (code "41") (name "RX") (class "Default")
      (node (ref "CN1") (pin "3") (pinfunction "3_3") (pintype "passive"))
      (node (ref "R9") (pin "2") (pinfunction "2_2") (pintype "passive"))
    )
    (net (code "42") (name "TX") (class "Default")
      (node (ref "CN1") (pin "4") (pinfunction "4_4") (pintype "passive"))
      (node (ref "R10") (pin "2") (pinfunction "2_2") (pintype "passive"))
    )
    (net (code "43") (name "VDD") (class "Default")
      (node (ref "C3") (pin "1") (pinfunction "1_1") (pintype "passive"))
      (node (ref "C4") (pin "1") (pinfunction "1_1") (pintype "passive"))
      (node (ref "C5") (pin "1") (pinfunction "1_1") (pintype "passive"))
      (node (ref "CN2") (pin "2") (pinfunction "VDD_2") (pintype "passive"))
      (node (ref "U1") (pin "1") (pinfunction "Vdd_1") (pintype "passive"))
      (node (ref "VR1") (pin "V-OUT") (pinfunction "Vo_V-OUT") (pintype "passive"))
    )
  )
)
